# Gateway_HUB.net
KiCad netlist of a schematic drawn in EAGLE
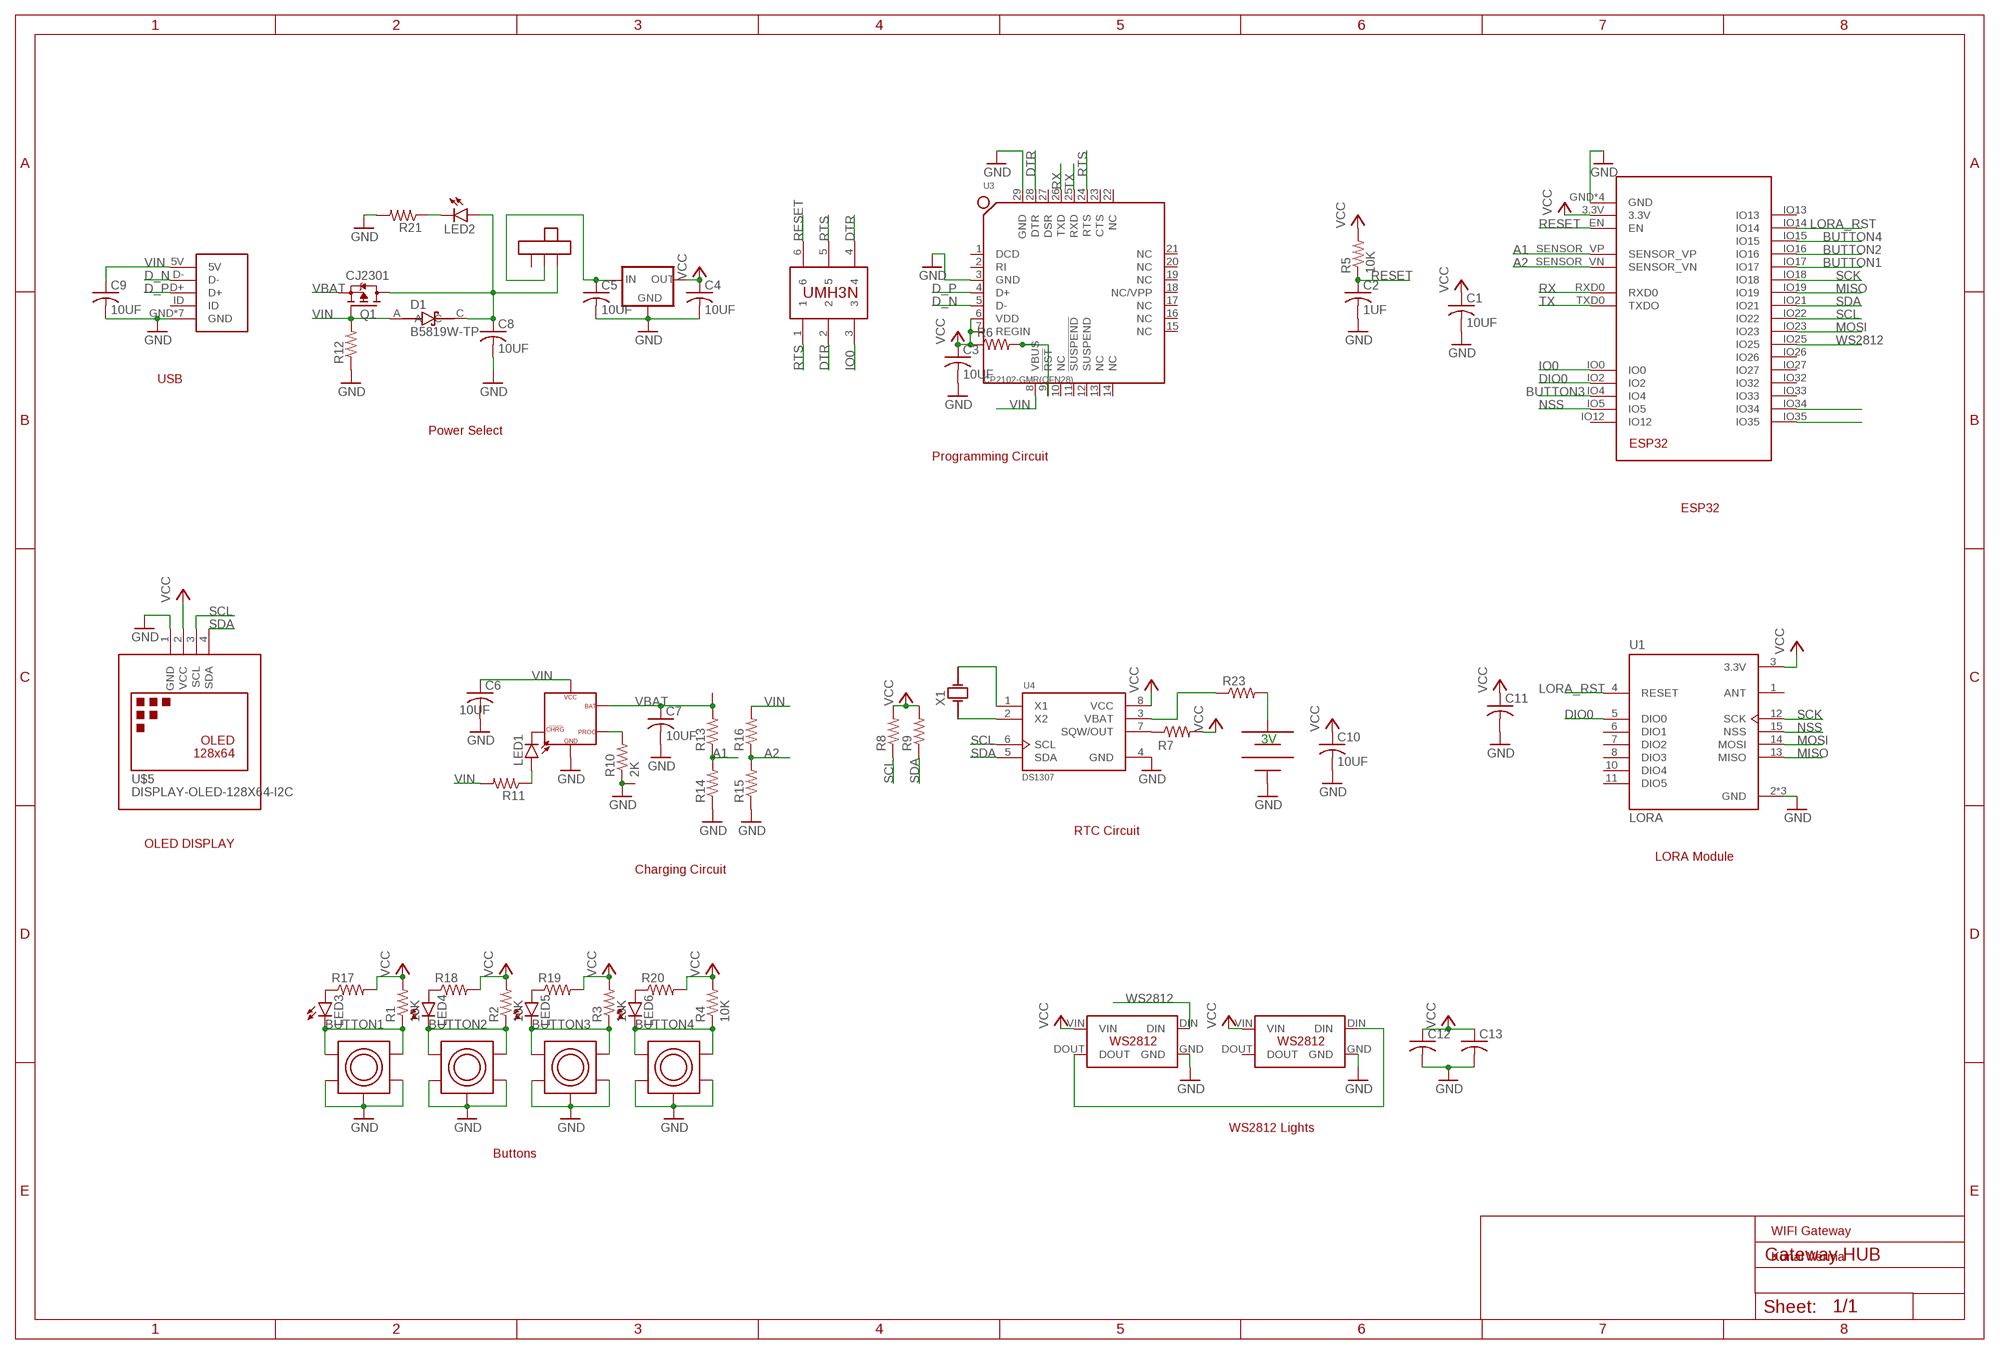
[diagram p0: schematic, sheet 1]

(export (version "E")
  (design (tool "Eeschema 10.0.6"))
  (components
    (comp (ref "C1")
      (value "10UF")
      (footprint "eagle-import:C0603")
      (libsource (lib "eagle-import") (part "C-USC0603"))
    )
    (comp (ref "C2")
      (value "1UF")
      (footprint "eagle-import:C0603")
      (libsource (lib "eagle-import") (part "C-USC0603"))
    )
    (comp (ref "C3")
      (value "10UF")
      (footprint "eagle-import:C0603")
      (libsource (lib "eagle-import") (part "C-USC0603"))
    )
    (comp (ref "C4")
      (value "10UF")
      (footprint "eagle-import:C0603")
      (libsource (lib "eagle-import") (part "C-USC0603"))
    )
    (comp (ref "C5")
      (value "10UF")
      (footprint "eagle-import:C0603")
      (libsource (lib "eagle-import") (part "C-USC0603"))
    )
    (comp (ref "C6")
      (value "10UF")
      (footprint "eagle-import:C0603")
      (libsource (lib "eagle-import") (part "C-USC0603"))
    )
    (comp (ref "C7")
      (value "10UF")
      (footprint "eagle-import:C0603")
      (libsource (lib "eagle-import") (part "C-USC0603"))
    )
    (comp (ref "C8")
      (value "10UF")
      (footprint "eagle-import:C0603")
      (libsource (lib "eagle-import") (part "C-USC0603"))
    )
    (comp (ref "C9")
      (value "10UF")
      (footprint "eagle-import:C0603")
      (libsource (lib "eagle-import") (part "C-USC0603"))
    )
    (comp (ref "C10")
      (value "10UF")
      (footprint "eagle-import:C0603")
      (libsource (lib "eagle-import") (part "C-USC0603"))
    )
    (comp (ref "C11")
      (value "C-USC0603")
      (footprint "eagle-import:C0603")
      (libsource (lib "eagle-import") (part "C-USC0603"))
    )
    (comp (ref "C12")
      (value "C-USC0603")
      (footprint "eagle-import:C0603")
      (libsource (lib "eagle-import") (part "C-USC0603"))
    )
    (comp (ref "C13")
      (value "C-USC0603")
      (footprint "eagle-import:C0603")
      (libsource (lib "eagle-import") (part "C-USC0603"))
    )
    (comp (ref "D1")
      (value "B5819W-TP")
      (footprint "eagle-import:SOD3716X135N")
      (fields (field (name "MF") "Micro Commercial"))
      (libsource (lib "eagle-import") (part "B5819W-TP"))
    )
    (comp (ref "IC1")
      (value "V_REG3.3MP")
      (footprint "eagle-import:SOT223")
      (fields (field (name "MF") "Texas Instruments") (field (name "MPN") "LM1117MP-3.3"))
      (libsource (lib "eagle-import") (part "V_REGMP3.3"))
    )
    (comp (ref "LED1")
      (value "LEDSML0603")
      (footprint "eagle-import:SML0603")
      (libsource (lib "eagle-import") (part "LEDSML0603"))
    )
    (comp (ref "LED2")
      (value "LEDSML0603")
      (footprint "eagle-import:SML0603")
      (libsource (lib "eagle-import") (part "LEDSML0603"))
    )
    (comp (ref "LED3")
      (value "LEDSML0603")
      (footprint "eagle-import:SML0603")
      (libsource (lib "eagle-import") (part "LEDSML0603"))
    )
    (comp (ref "LED4")
      (value "LEDSML0603")
      (footprint "eagle-import:SML0603")
      (libsource (lib "eagle-import") (part "LEDSML0603"))
    )
    (comp (ref "LED5")
      (value "LEDSML0603")
      (footprint "eagle-import:SML0603")
      (libsource (lib "eagle-import") (part "LEDSML0603"))
    )
    (comp (ref "LED6")
      (value "LEDSML0603")
      (footprint "eagle-import:SML0603")
      (libsource (lib "eagle-import") (part "LEDSML0603"))
    )
    (comp (ref "Q1")
      (value "CJ2301")
      (footprint "eagle-import:SOT95P230X110-3N")
      (fields (field (name "MF") "Nexperia USA Inc.") (field (name "MP") "PMV65XP,215"))
      (libsource (lib "eagle-import") (part "CJ2301"))
    )
    (comp (ref "R1")
      (value "10K")
      (footprint "eagle-import:R0603")
      (libsource (lib "eagle-import") (part "R-US_R0603"))
    )
    (comp (ref "R2")
      (value "10K")
      (footprint "eagle-import:R0603")
      (libsource (lib "eagle-import") (part "R-US_R0603"))
    )
    (comp (ref "R3")
      (value "10K")
      (footprint "eagle-import:R0603")
      (libsource (lib "eagle-import") (part "R-US_R0603"))
    )
    (comp (ref "R4")
      (value "10K")
      (footprint "eagle-import:R0603")
      (libsource (lib "eagle-import") (part "R-US_R0603"))
    )
    (comp (ref "R5")
      (value "10K")
      (footprint "eagle-import:R0603")
      (libsource (lib "eagle-import") (part "R-US_R0603"))
    )
    (comp (ref "R6")
      (value "R-US_R0603")
      (footprint "eagle-import:R0603")
      (libsource (lib "eagle-import") (part "R-US_R0603"))
    )
    (comp (ref "R7")
      (value "R-US_R0603")
      (footprint "eagle-import:R0603")
      (libsource (lib "eagle-import") (part "R-US_R0603"))
    )
    (comp (ref "R8")
      (value "R-US_R0603")
      (footprint "eagle-import:R0603")
      (libsource (lib "eagle-import") (part "R-US_R0603"))
    )
    (comp (ref "R9")
      (value "R-US_R0603")
      (footprint "eagle-import:R0603")
      (libsource (lib "eagle-import") (part "R-US_R0603"))
    )
    (comp (ref "R10")
      (value "2K")
      (footprint "eagle-import:R0603")
      (libsource (lib "eagle-import") (part "R-US_R0603"))
    )
    (comp (ref "R11")
      (value "R-US_R0603")
      (footprint "eagle-import:R0603")
      (libsource (lib "eagle-import") (part "R-US_R0603"))
    )
    (comp (ref "R12")
      (value "R-US_R0603")
      (footprint "eagle-import:R0603")
      (libsource (lib "eagle-import") (part "R-US_R0603"))
    )
    (comp (ref "R13")
      (value "R-US_R0603")
      (footprint "eagle-import:R0603")
      (libsource (lib "eagle-import") (part "R-US_R0603"))
    )
    (comp (ref "R14")
      (value "R-US_R0603")
      (footprint "eagle-import:R0603")
      (libsource (lib "eagle-import") (part "R-US_R0603"))
    )
    (comp (ref "R15")
      (value "R-US_R0603")
      (footprint "eagle-import:R0603")
      (libsource (lib "eagle-import") (part "R-US_R0603"))
    )
    (comp (ref "R16")
      (value "R-US_R0603")
      (footprint "eagle-import:R0603")
      (libsource (lib "eagle-import") (part "R-US_R0603"))
    )
    (comp (ref "R17")
      (value "R-US_R0603")
      (footprint "eagle-import:R0603")
      (libsource (lib "eagle-import") (part "R-US_R0603"))
    )
    (comp (ref "R18")
      (value "R-US_R0603")
      (footprint "eagle-import:R0603")
      (libsource (lib "eagle-import") (part "R-US_R0603"))
    )
    (comp (ref "R19")
      (value "R-US_R0603")
      (footprint "eagle-import:R0603")
      (libsource (lib "eagle-import") (part "R-US_R0603"))
    )
    (comp (ref "R20")
      (value "R-US_R0603")
      (footprint "eagle-import:R0603")
      (libsource (lib "eagle-import") (part "R-US_R0603"))
    )
    (comp (ref "R21")
      (value "R-US_R0603")
      (footprint "eagle-import:R0603")
      (libsource (lib "eagle-import") (part "R-US_R0603"))
    )
    (comp (ref "R23")
      (value "R-US_R0603")
      (footprint "eagle-import:R0603")
      (libsource (lib "eagle-import") (part "R-US_R0603"))
    )
    (comp (ref "U$1")
      (value "PUSHBUTTON")
      (footprint "eagle-import:B3W-4105")
      (libsource (lib "eagle-import") (part "PUSHBUTTON"))
    )
    (comp (ref "U$2")
      (value "PUSHBUTTON")
      (footprint "eagle-import:B3W-4105")
      (libsource (lib "eagle-import") (part "PUSHBUTTON"))
    )
    (comp (ref "U$3")
      (value "PUSHBUTTON")
      (footprint "eagle-import:B3W-4105")
      (libsource (lib "eagle-import") (part "PUSHBUTTON"))
    )
    (comp (ref "U$4")
      (value "PUSHBUTTON")
      (footprint "eagle-import:B3W-4105")
      (libsource (lib "eagle-import") (part "PUSHBUTTON"))
    )
    (comp (ref "U$5")
      (value "DISPLAY-OLED-128X64-I2C")
      (footprint "eagle-import:DISPLAY-OLED-128X64-I2C")
      (libsource (lib "eagle-import") (part "DISPLAY-OLED-128X64-I2C"))
    )
    (comp (ref "U$6")
      (value "COIN_CELL_HOLDER")
      (footprint "eagle-import:CR2032-BS-6-1")
      (libsource (lib "eagle-import") (part "COIN_CELL_HOLDER"))
    )
    (comp (ref "U$7")
      (value "UMH3N")
      (footprint "eagle-import:UMH3N")
      (libsource (lib "eagle-import") (part "UMH3N"))
    )
    (comp (ref "U$8")
      (value "MICROUSB")
      (footprint "eagle-import:USB")
      (libsource (lib "eagle-import") (part "MICROUSB"))
    )
    (comp (ref "U$9")
      (value "SELF-TOOGLE-SWITCH")
      (footprint "eagle-import:SELF-TOOGLE-SWITCH")
      (libsource (lib "eagle-import") (part "SELF-TOOGLE-SWITCH"))
    )
    (comp (ref "U$10")
      (value "PAD")
      (footprint "eagle-import:PADS")
      (libsource (lib "eagle-import") (part "PAD"))
    )
    (comp (ref "U$11")
      (value "PAD")
      (footprint "eagle-import:PADS")
      (libsource (lib "eagle-import") (part "PAD"))
    )
    (comp (ref "U$12")
      (value "WS2812SMD-2020")
      (footprint "eagle-import:SMD-2020")
      (libsource (lib "eagle-import") (part "WS2812SMD-2020"))
    )
    (comp (ref "U$13")
      (value "WS2812SMD-2020")
      (footprint "eagle-import:SMD-2020")
      (libsource (lib "eagle-import") (part "WS2812SMD-2020"))
    )
    (comp (ref "U1")
      (value "LORA")
      (footprint "eagle-import:XCVR_RA-01H")
      (fields (field (name "MF") "AI-Thinker") (field (name "MP") "RA-01H"))
      (libsource (lib "eagle-import") (part "LORA"))
    )
    (comp (ref "U2")
      (value "ESP32")
      (footprint "eagle-import:MODULE_ESP-WROOM-32")
      (libsource (lib "eagle-import") (part "ESP32"))
    )
    (comp (ref "U3")
      (value "CP2102-GMR(QFN28)")
      (footprint "eagle-import:QFN28G_0.5-5X5MM")
      (fields (field (name "MF") "Silicon") (field (name "MP") "CP2102-GMR"))
      (libsource (lib "eagle-import") (part "CP2102-GMR(QFN28)"))
    )
    (comp (ref "U4")
      (value "DS1307")
      (footprint "eagle-import:SOIC127P600X175-8N")
      (fields (field (name "MF") "Maxim Integrated") (field (name "MP") "DS1307Z"))
      (libsource (lib "eagle-import") (part "DS1307"))
    )
    (comp (ref "U5")
      (value "TP4054")
      (footprint "eagle-import:SOT23-3")
      (fields (field (name "MF") "Richtek USA") (field (name "MP") "RT9193-33GB"))
      (libsource (lib "eagle-import") (part "TP4054"))
    )
    (comp (ref "X1")
      (value "CRYSTAL_38T-32.768KHZ")
      (footprint "eagle-import:XTAL_AB38T-32.768KHZ")
      (fields (field (name "MF") "Abracon") (field (name "MP") "AB38T-32.768KHZ"))
      (libsource (lib "eagle-import") (part "CRYSTAL_38T-32.768KHZ"))
    )
  )
  (nets
    (net (code "1") (name "/A1") (class "Default")
      (node (ref "R13") (pin "1") (pinfunction "1_1") (pintype "passive"))
      (node (ref "R14") (pin "2") (pinfunction "2_2") (pintype "passive"))
      (node (ref "U2") (pin "SENSOR_VP") (pinfunction "SENSOR_VP_SENSOR_VP") (pintype "bidirectional"))
    )
    (net (code "2") (name "/A2") (class "Default")
      (node (ref "R15") (pin "2") (pinfunction "2_2") (pintype "passive"))
      (node (ref "R16") (pin "1") (pinfunction "1_1") (pintype "passive"))
      (node (ref "U2") (pin "SENSOR_VN") (pinfunction "SENSOR_VN_SENSOR_VN") (pintype "bidirectional"))
    )
    (net (code "3") (name "/BUTTON1") (class "Default")
      (node (ref "LED3") (pin "C") (pinfunction "C_C") (pintype "passive"))
      (node (ref "R1") (pin "1") (pinfunction "1_1") (pintype "passive"))
      (node (ref "U$1") (pin "P$1") (pinfunction "P$1_P$1") (pintype "bidirectional"))
      (node (ref "U$1") (pin "P$4") (pinfunction "P$4_P$4") (pintype "bidirectional"))
      (node (ref "U2") (pin "IO17") (pinfunction "IO17_IO17") (pintype "bidirectional"))
    )
    (net (code "4") (name "/BUTTON2") (class "Default")
      (node (ref "LED4") (pin "C") (pinfunction "C_C") (pintype "passive"))
      (node (ref "R2") (pin "1") (pinfunction "1_1") (pintype "passive"))
      (node (ref "U$2") (pin "P$1") (pinfunction "P$1_P$1") (pintype "bidirectional"))
      (node (ref "U$2") (pin "P$4") (pinfunction "P$4_P$4") (pintype "bidirectional"))
      (node (ref "U2") (pin "IO16") (pinfunction "IO16_IO16") (pintype "bidirectional"))
    )
    (net (code "5") (name "/BUTTON3") (class "Default")
      (node (ref "LED5") (pin "C") (pinfunction "C_C") (pintype "passive"))
      (node (ref "R3") (pin "1") (pinfunction "1_1") (pintype "passive"))
      (node (ref "U$3") (pin "P$1") (pinfunction "P$1_P$1") (pintype "bidirectional"))
      (node (ref "U$3") (pin "P$4") (pinfunction "P$4_P$4") (pintype "bidirectional"))
      (node (ref "U2") (pin "IO4") (pinfunction "IO4_IO4") (pintype "bidirectional"))
    )
    (net (code "6") (name "/BUTTON4") (class "Default")
      (node (ref "LED6") (pin "C") (pinfunction "C_C") (pintype "passive"))
      (node (ref "R4") (pin "1") (pinfunction "1_1") (pintype "passive"))
      (node (ref "U$4") (pin "P$1") (pinfunction "P$1_P$1") (pintype "bidirectional"))
      (node (ref "U$4") (pin "P$4") (pinfunction "P$4_P$4") (pintype "bidirectional"))
      (node (ref "U2") (pin "IO15") (pinfunction "IO15_IO15") (pintype "bidirectional"))
    )
    (net (code "7") (name "/DIO0") (class "Default")
      (node (ref "U1") (pin "5") (pinfunction "DIO0_5") (pintype "bidirectional"))
      (node (ref "U2") (pin "IO2") (pinfunction "IO2_IO2") (pintype "bidirectional"))
    )
    (net (code "8") (name "/DTR") (class "Default")
      (node (ref "U$7") (pin "2") (pinfunction "2_2") (pintype "bidirectional"))
      (node (ref "U$7") (pin "4") (pinfunction "4_4") (pintype "bidirectional"))
      (node (ref "U3") (pin "28") (pinfunction "DTR_28") (pintype "bidirectional"))
    )
    (net (code "9") (name "/D_N") (class "Default")
      (node (ref "U$8") (pin "D-") (pinfunction "D-_D-") (pintype "bidirectional"))
      (node (ref "U3") (pin "5") (pinfunction "D-_5") (pintype "bidirectional"))
    )
    (net (code "10") (name "/D_P") (class "Default")
      (node (ref "U$8") (pin "D+") (pinfunction "D+_D+") (pintype "bidirectional"))
      (node (ref "U3") (pin "4") (pinfunction "D+_4") (pintype "bidirectional"))
    )
    (net (code "11") (name "/IO0") (class "Default")
      (node (ref "U$7") (pin "3") (pinfunction "3_3") (pintype "bidirectional"))
      (node (ref "U2") (pin "IO0") (pinfunction "IO0_IO0") (pintype "bidirectional"))
    )
    (net (code "12") (name "/LORA_RST") (class "Default")
      (node (ref "U1") (pin "4") (pinfunction "RESET_4") (pintype "input"))
      (node (ref "U2") (pin "IO14") (pinfunction "IO14_IO14") (pintype "bidirectional"))
    )
    (net (code "13") (name "/MISO") (class "Default")
      (node (ref "U1") (pin "13") (pinfunction "MISO_13") (pintype "output"))
      (node (ref "U2") (pin "IO19") (pinfunction "IO19_IO19") (pintype "bidirectional"))
    )
    (net (code "14") (name "/MOSI") (class "Default")
      (node (ref "U1") (pin "14") (pinfunction "MOSI_14") (pintype "input"))
      (node (ref "U2") (pin "IO23") (pinfunction "IO23_IO23") (pintype "bidirectional"))
    )
    (net (code "15") (name "/NSS") (class "Default")
      (node (ref "U1") (pin "15") (pinfunction "NSS_15") (pintype "input"))
      (node (ref "U2") (pin "IO5") (pinfunction "IO5_IO5") (pintype "bidirectional"))
    )
    (net (code "16") (name "/RESET") (class "Default")
      (node (ref "C2") (pin "1") (pinfunction "1_1") (pintype "passive"))
      (node (ref "R5") (pin "1") (pinfunction "1_1") (pintype "passive"))
      (node (ref "U$7") (pin "6") (pinfunction "6_6") (pintype "bidirectional"))
      (node (ref "U2") (pin "EN") (pinfunction "EN_EN") (pintype "bidirectional"))
    )
    (net (code "17") (name "/RTS") (class "Default")
      (node (ref "U$7") (pin "1") (pinfunction "1_1") (pintype "bidirectional"))
      (node (ref "U$7") (pin "5") (pinfunction "5_5") (pintype "bidirectional"))
      (node (ref "U3") (pin "24") (pinfunction "RTS_24") (pintype "bidirectional"))
    )
    (net (code "18") (name "/RX") (class "Default")
      (node (ref "U2") (pin "RXD0") (pinfunction "RXD0_RXD0") (pintype "bidirectional"))
      (node (ref "U3") (pin "26") (pinfunction "TXD_26") (pintype "bidirectional"))
    )
    (net (code "19") (name "/SCK") (class "Default")
      (node (ref "U1") (pin "12") (pinfunction "SCK_12") (pintype "input"))
      (node (ref "U2") (pin "IO18") (pinfunction "IO18_IO18") (pintype "bidirectional"))
    )
    (net (code "20") (name "/SCL") (class "Default")
      (node (ref "R8") (pin "1") (pinfunction "1_1") (pintype "passive"))
      (node (ref "U$5") (pin "3") (pinfunction "SCL_3") (pintype "bidirectional"))
      (node (ref "U2") (pin "IO22") (pinfunction "IO22_IO22") (pintype "bidirectional"))
      (node (ref "U4") (pin "6") (pinfunction "SCL_6") (pintype "input"))
    )
    (net (code "21") (name "/SDA") (class "Default")
      (node (ref "R9") (pin "1") (pinfunction "1_1") (pintype "passive"))
      (node (ref "U$5") (pin "4") (pinfunction "SDA_4") (pintype "bidirectional"))
      (node (ref "U2") (pin "IO21") (pinfunction "IO21_IO21") (pintype "bidirectional"))
      (node (ref "U4") (pin "5") (pinfunction "SDA_5") (pintype "bidirectional"))
    )
    (net (code "22") (name "/TX") (class "Default")
      (node (ref "U2") (pin "TXD0") (pinfunction "TXDO_TXD0") (pintype "bidirectional"))
      (node (ref "U3") (pin "25") (pinfunction "RXD_25") (pintype "bidirectional"))
    )
    (net (code "23") (name "/VBAT") (class "Default")
      (node (ref "C7") (pin "1") (pinfunction "1_1") (pintype "passive"))
      (node (ref "Q1") (pin "2") (pinfunction "S_2") (pintype "passive"))
      (node (ref "R13") (pin "2") (pinfunction "2_2") (pintype "passive"))
      (node (ref "U$10") (pin "P$1") (pinfunction "P$1_P$1") (pintype "bidirectional"))
      (node (ref "U5") (pin "3") (pinfunction "3_3") (pintype "bidirectional"))
    )
    (net (code "24") (name "/VIN") (class "Default")
      (node (ref "C6") (pin "1") (pinfunction "1_1") (pintype "passive"))
      (node (ref "C9") (pin "1") (pinfunction "1_1") (pintype "passive"))
      (node (ref "D1") (pin "A") (pinfunction "A_A") (pintype "passive"))
      (node (ref "Q1") (pin "1") (pinfunction "G_1") (pintype "passive"))
      (node (ref "R11") (pin "2") (pinfunction "2_2") (pintype "passive"))
      (node (ref "R12") (pin "2") (pinfunction "2_2") (pintype "passive"))
      (node (ref "R16") (pin "2") (pinfunction "2_2") (pintype "passive"))
      (node (ref "U$8") (pin "5V") (pinfunction "5V_5V") (pintype "bidirectional"))
      (node (ref "U3") (pin "8") (pinfunction "VBUS_8") (pintype "bidirectional"))
      (node (ref "U5") (pin "4") (pinfunction "4_4") (pintype "bidirectional"))
    )
    (net (code "25") (name "/WS2812") (class "Default")
      (node (ref "U$12") (pin "DIN") (pinfunction "DIN_DIN") (pintype "bidirectional"))
      (node (ref "U2") (pin "IO25") (pinfunction "IO25_IO25") (pintype "bidirectional"))
    )
    (net (code "26") (name "GND") (class "Default")
      (node (ref "C1") (pin "2") (pinfunction "2_2") (pintype "passive"))
      (node (ref "C10") (pin "2") (pinfunction "2_2") (pintype "passive"))
      (node (ref "C11") (pin "2") (pinfunction "2_2") (pintype "passive"))
      (node (ref "C12") (pin "2") (pinfunction "2_2") (pintype "passive"))
      (node (ref "C13") (pin "2") (pinfunction "2_2") (pintype "passive"))
      (node (ref "C2") (pin "2") (pinfunction "2_2") (pintype "passive"))
      (node (ref "C3") (pin "2") (pinfunction "2_2") (pintype "passive"))
      (node (ref "C4") (pin "2") (pinfunction "2_2") (pintype "passive"))
      (node (ref "C5") (pin "2") (pinfunction "2_2") (pintype "passive"))
      (node (ref "C6") (pin "2") (pinfunction "2_2") (pintype "passive"))
      (node (ref "C7") (pin "2") (pinfunction "2_2") (pintype "passive"))
      (node (ref "C8") (pin "2") (pinfunction "2_2") (pintype "passive"))
      (node (ref "C9") (pin "2") (pinfunction "2_2") (pintype "passive"))
      (node (ref "IC1") (pin "GND") (pinfunction "GND_GND") (pintype "input"))
      (node (ref "R10") (pin "1") (pinfunction "1_1") (pintype "passive"))
      (node (ref "R12") (pin "1") (pinfunction "1_1") (pintype "passive"))
      (node (ref "R14") (pin "1") (pinfunction "1_1") (pintype "passive"))
      (node (ref "R15") (pin "1") (pinfunction "1_1") (pintype "passive"))
      (node (ref "R21") (pin "2") (pinfunction "2_2") (pintype "passive"))
      (node (ref "U$1") (pin "P$2") (pinfunction "P$2_P$2") (pintype "bidirectional"))
      (node (ref "U$1") (pin "P$3") (pinfunction "P$3_P$3") (pintype "bidirectional"))
      (node (ref "U$1") (pin "P$5") (pinfunction "P$5_P$5") (pintype "bidirectional"))
      (node (ref "U$11") (pin "P$1") (pinfunction "P$1_P$1") (pintype "bidirectional"))
      (node (ref "U$12") (pin "GND") (pinfunction "GND_GND") (pintype "bidirectional"))
      (node (ref "U$13") (pin "GND") (pinfunction "GND_GND") (pintype "bidirectional"))
      (node (ref "U$2") (pin "P$2") (pinfunction "P$2_P$2") (pintype "bidirectional"))
      (node (ref "U$2") (pin "P$3") (pinfunction "P$3_P$3") (pintype "bidirectional"))
      (node (ref "U$2") (pin "P$5") (pinfunction "P$5_P$5") (pintype "bidirectional"))
      (node (ref "U$3") (pin "P$2") (pinfunction "P$2_P$2") (pintype "bidirectional"))
      (node (ref "U$3") (pin "P$3") (pinfunction "P$3_P$3") (pintype "bidirectional"))
      (node (ref "U$3") (pin "P$5") (pinfunction "P$5_P$5") (pintype "bidirectional"))
      (node (ref "U$4") (pin "P$2") (pinfunction "P$2_P$2") (pintype "bidirectional"))
      (node (ref "U$4") (pin "P$3") (pinfunction "P$3_P$3") (pintype "bidirectional"))
      (node (ref "U$4") (pin "P$5") (pinfunction "P$5_P$5") (pintype "bidirectional"))
      (node (ref "U$5") (pin "1") (pinfunction "GND_1") (pintype "power_in"))
      (node (ref "U$6") (pin "-") (pinfunction "-_-") (pintype "bidirectional"))
      (node (ref "U$8") (pin "GND") (pinfunction "GND_GND") (pintype "bidirectional"))
      (node (ref "U$8") (pin "GND1") (pinfunction "GND_GND1") (pintype "bidirectional"))
      (node (ref "U$8") (pin "GND2") (pinfunction "GND_GND2") (pintype "bidirectional"))
      (node (ref "U$8") (pin "GND3") (pinfunction "GND_GND3") (pintype "bidirectional"))
      (node (ref "U$8") (pin "GND4") (pinfunction "GND_GND4") (pintype "bidirectional"))
      (node (ref "U$8") (pin "GND5") (pinfunction "GND_GND5") (pintype "bidirectional"))
      (node (ref "U$8") (pin "GND6") (pinfunction "GND_GND6") (pintype "bidirectional"))
      (node (ref "U1") (pin "16") (pinfunction "GND_16") (pintype "power_in"))
      (node (ref "U1") (pin "2") (pinfunction "GND_2") (pintype "power_in"))
      (node (ref "U1") (pin "9") (pinfunction "GND_9") (pintype "power_in"))
      (node (ref "U2") (pin "GND") (pinfunction "GND_GND") (pintype "bidirectional"))
      (node (ref "U2") (pin "GND1") (pinfunction "GND_GND1") (pintype "bidirectional"))
      (node (ref "U2") (pin "GND2") (pinfunction "GND_GND2") (pintype "bidirectional"))
      (node (ref "U2") (pin "GND3") (pinfunction "GND_GND3") (pintype "bidirectional"))
      (node (ref "U3") (pin "29") (pinfunction "GND_29") (pintype "bidirectional"))
      (node (ref "U3") (pin "3") (pinfunction "GND_3") (pintype "bidirectional"))
      (node (ref "U4") (pin "4") (pinfunction "GND_4") (pintype "power_in"))
      (node (ref "U5") (pin "2") (pinfunction "2_2") (pintype "bidirectional"))
    )
    (net (code "27") (name "Net-(IC1-IN)") (class "Default")
      (node (ref "C5") (pin "1") (pinfunction "1_1") (pintype "passive"))
      (node (ref "IC1") (pin "VIN") (pinfunction "IN_VIN") (pintype "input"))
      (node (ref "U$9") (pin "2") (pinfunction "2_2") (pintype "bidirectional"))
    )
    (net (code "28") (name "Net-(LED1-PadA)") (class "Default")
      (node (ref "LED1") (pin "A") (pinfunction "A_A") (pintype "passive"))
      (node (ref "R11") (pin "1") (pinfunction "1_1") (pintype "passive"))
    )
    (net (code "29") (name "Net-(LED1-PadC)") (class "Default")
      (node (ref "LED1") (pin "C") (pinfunction "C_C") (pintype "passive"))
      (node (ref "U5") (pin "1") (pinfunction "1_1") (pintype "bidirectional"))
    )
    (net (code "30") (name "Net-(LED2-PadC)") (class "Default")
      (node (ref "LED2") (pin "C") (pinfunction "C_C") (pintype "passive"))
      (node (ref "R21") (pin "1") (pinfunction "1_1") (pintype "passive"))
    )
    (net (code "31") (name "Net-(LED3-PadA)") (class "Default")
      (node (ref "LED3") (pin "A") (pinfunction "A_A") (pintype "passive"))
      (node (ref "R17") (pin "1") (pinfunction "1_1") (pintype "passive"))
    )
    (net (code "32") (name "Net-(LED4-PadA)") (class "Default")
      (node (ref "LED4") (pin "A") (pinfunction "A_A") (pintype "passive"))
      (node (ref "R18") (pin "1") (pinfunction "1_1") (pintype "passive"))
    )
    (net (code "33") (name "Net-(LED5-PadA)") (class "Default")
      (node (ref "LED5") (pin "A") (pinfunction "A_A") (pintype "passive"))
      (node (ref "R19") (pin "1") (pinfunction "1_1") (pintype "passive"))
    )
    (net (code "34") (name "Net-(LED6-PadA)") (class "Default")
      (node (ref "LED6") (pin "A") (pinfunction "A_A") (pintype "passive"))
      (node (ref "R20") (pin "1") (pinfunction "1_1") (pintype "passive"))
    )
    (net (code "35") (name "Net-(Q1-D)") (class "Default")
      (node (ref "C8") (pin "1") (pinfunction "1_1") (pintype "passive"))
      (node (ref "D1") (pin "C") (pinfunction "C_C") (pintype "passive"))
      (node (ref "LED2") (pin "A") (pinfunction "A_A") (pintype "passive"))
      (node (ref "Q1") (pin "3") (pinfunction "D_3") (pintype "passive"))
      (node (ref "U$9") (pin "3") (pinfunction "3_3") (pintype "bidirectional"))
    )
    (net (code "36") (name "Net-(R10-Pad2)") (class "Default")
      (node (ref "R10") (pin "2") (pinfunction "2_2") (pintype "passive"))
      (node (ref "U5") (pin "5") (pinfunction "5_5") (pintype "bidirectional"))
    )
    (net (code "37") (name "Net-(R23-Pad2)") (class "Default")
      (node (ref "R23") (pin "2") (pinfunction "2_2") (pintype "passive"))
      (node (ref "U$6") (pin "+") (pinfunction "+_+") (pintype "bidirectional"))
    )
    (net (code "38") (name "Net-(U$12-PadDOUT)") (class "Default")
      (node (ref "U$12") (pin "DOUT") (pinfunction "DOUT_DOUT") (pintype "bidirectional"))
      (node (ref "U$13") (pin "DIN") (pinfunction "DIN_DIN") (pintype "bidirectional"))
    )
    (net (code "39") (name "Net-(U3-~{RST})") (class "Default")
      (node (ref "R6") (pin "2") (pinfunction "2_2") (pintype "passive"))
      (node (ref "U3") (pin "9") (pinfunction "~{RST}_9") (pintype "bidirectional"))
    )
    (net (code "40") (name "Net-(U4-SQW{slash}OUT)") (class "Default")
      (node (ref "R7") (pin "1") (pinfunction "1_1") (pintype "passive"))
      (node (ref "U4") (pin "7") (pinfunction "SQW/OUT_7") (pintype "output"))
    )
    (net (code "41") (name "Net-(U4-VBAT)") (class "Default")
      (node (ref "R23") (pin "1") (pinfunction "1_1") (pintype "passive"))
      (node (ref "U4") (pin "3") (pinfunction "VBAT_3") (pintype "power_in"))
    )
    (net (code "42") (name "Net-(U4-X1)") (class "Default")
      (node (ref "U4") (pin "1") (pinfunction "X1_1") (pintype "input"))
      (node (ref "X1") (pin "2") (pinfunction "2_2") (pintype "passive"))
    )
    (net (code "43") (name "Net-(U4-X2)") (class "Default")
      (node (ref "U4") (pin "2") (pinfunction "X2_2") (pintype "input"))
      (node (ref "X1") (pin "1") (pinfunction "1_1") (pintype "passive"))
    )
    (net (code "44") (name "VCC") (class "Default")
      (node (ref "C1") (pin "1") (pinfunction "1_1") (pintype "passive"))
      (node (ref "C10") (pin "1") (pinfunction "1_1") (pintype "passive"))
      (node (ref "C11") (pin "1") (pinfunction "1_1") (pintype "passive"))
      (node (ref "C12") (pin "1") (pinfunction "1_1") (pintype "passive"))
      (node (ref "C13") (pin "1") (pinfunction "1_1") (pintype "passive"))
      (node (ref "C3") (pin "1") (pinfunction "1_1") (pintype "passive"))
      (node (ref "C4") (pin "1") (pinfunction "1_1") (pintype "passive"))
      (node (ref "IC1") (pin "VOUT") (pinfunction "OUT_VOUT") (pintype "passive"))
      (node (ref "IC1") (pin "VOUT1") (pinfunction "OUT_VOUT1") (pintype "passive"))
      (node (ref "R1") (pin "2") (pinfunction "2_2") (pintype "passive"))
      (node (ref "R17") (pin "2") (pinfunction "2_2") (pintype "passive"))
      (node (ref "R18") (pin "2") (pinfunction "2_2") (pintype "passive"))
      (node (ref "R19") (pin "2") (pinfunction "2_2") (pintype "passive"))
      (node (ref "R2") (pin "2") (pinfunction "2_2") (pintype "passive"))
      (node (ref "R20") (pin "2") (pinfunction "2_2") (pintype "passive"))
      (node (ref "R3") (pin "2") (pinfunction "2_2") (pintype "passive"))
      (node (ref "R4") (pin "2") (pinfunction "2_2") (pintype "passive"))
      (node (ref "R5") (pin "2") (pinfunction "2_2") (pintype "passive"))
      (node (ref "R6") (pin "1") (pinfunction "1_1") (pintype "passive"))
      (node (ref "R7") (pin "2") (pinfunction "2_2") (pintype "passive"))
      (node (ref "R8") (pin "2") (pinfunction "2_2") (pintype "passive"))
      (node (ref "R9") (pin "2") (pinfunction "2_2") (pintype "passive"))
      (node (ref "U$12") (pin "VIN") (pinfunction "VIN_VIN") (pintype "bidirectional"))
      (node (ref "U$13") (pin "VIN") (pinfunction "VIN_VIN") (pintype "bidirectional"))
      (node (ref "U$5") (pin "2") (pinfunction "VCC_2") (pintype "power_in"))
      (node (ref "U1") (pin "3") (pinfunction "3.3V_3") (pintype "power_in"))
      (node (ref "U2") (pin "3.3V") (pinfunction "3.3V_3.3V") (pintype "bidirectional"))
      (node (ref "U3") (pin "6") (pinfunction "VDD_6") (pintype "bidirectional"))
      (node (ref "U3") (pin "7") (pinfunction "REGIN_7") (pintype "bidirectional"))
      (node (ref "U4") (pin "8") (pinfunction "VCC_8") (pintype "power_in"))
    )
    (net (code "45") (name "unconnected-(U$8-PadID)") (class "Default")
      (node (ref "U$8") (pin "ID") (pinfunction "ID_ID") (pintype "bidirectional"))
    )
    (net (code "46") (name "unconnected-(U$9-Pad1)") (class "Default")
      (node (ref "U$9") (pin "1") (pinfunction "1_1") (pintype "bidirectional"))
    )
    (net (code "47") (name "unconnected-(U$13-PadDOUT)") (class "Default")
      (node (ref "U$13") (pin "DOUT") (pinfunction "DOUT_DOUT") (pintype "bidirectional"))
    )
    (net (code "48") (name "unconnected-(U1-ANT-Pad1)") (class "Default")
      (node (ref "U1") (pin "1") (pinfunction "ANT_1") (pintype "bidirectional"))
    )
    (net (code "49") (name "unconnected-(U1-DIO1-Pad6)") (class "Default")
      (node (ref "U1") (pin "6") (pinfunction "DIO1_6") (pintype "bidirectional"))
    )
    (net (code "50") (name "unconnected-(U1-DIO2-Pad7)") (class "Default")
      (node (ref "U1") (pin "7") (pinfunction "DIO2_7") (pintype "bidirectional"))
    )
    (net (code "51") (name "unconnected-(U1-DIO3-Pad8)") (class "Default")
      (node (ref "U1") (pin "8") (pinfunction "DIO3_8") (pintype "bidirectional"))
    )
    (net (code "52") (name "unconnected-(U1-DIO4-Pad10)") (class "Default")
      (node (ref "U1") (pin "10") (pinfunction "DIO4_10") (pintype "bidirectional"))
    )
    (net (code "53") (name "unconnected-(U1-DIO5-Pad11)") (class "Default")
      (node (ref "U1") (pin "11") (pinfunction "DIO5_11") (pintype "bidirectional"))
    )
    (net (code "54") (name "unconnected-(U2-PadIO12)") (class "Default")
      (node (ref "U2") (pin "IO12") (pinfunction "IO12_IO12") (pintype "bidirectional"))
    )
    (net (code "55") (name "unconnected-(U2-PadIO13)") (class "Default")
      (node (ref "U2") (pin "IO13") (pinfunction "IO13_IO13") (pintype "bidirectional"))
    )
    (net (code "56") (name "unconnected-(U2-PadIO26)") (class "Default")
      (node (ref "U2") (pin "IO26") (pinfunction "IO26_IO26") (pintype "bidirectional"))
    )
    (net (code "57") (name "unconnected-(U2-PadIO27)") (class "Default")
      (node (ref "U2") (pin "IO27") (pinfunction "IO27_IO27") (pintype "bidirectional"))
    )
    (net (code "58") (name "unconnected-(U2-PadIO32)") (class "Default")
      (node (ref "U2") (pin "IO32") (pinfunction "IO32_IO32") (pintype "bidirectional"))
    )
    (net (code "59") (name "unconnected-(U2-PadIO33)") (class "Default")
      (node (ref "U2") (pin "IO33") (pinfunction "IO33_IO33") (pintype "bidirectional"))
    )
    (net (code "60") (name "unconnected-(U2-PadIO34)") (class "Default")
      (node (ref "U2") (pin "IO34") (pinfunction "IO34_IO34") (pintype "bidirectional"))
    )
    (net (code "61") (name "unconnected-(U2-PadIO35)") (class "Default")
      (node (ref "U2") (pin "IO35") (pinfunction "IO35_IO35") (pintype "bidirectional"))
    )
    (net (code "62") (name "unconnected-(U3-CTS-Pad23)") (class "Default")
      (node (ref "U3") (pin "23") (pinfunction "CTS_23") (pintype "bidirectional"))
    )
    (net (code "63") (name "unconnected-(U3-DCD-Pad1)") (class "Default")
      (node (ref "U3") (pin "1") (pinfunction "DCD_1") (pintype "bidirectional"))
    )
    (net (code "64") (name "unconnected-(U3-DSR-Pad27)") (class "Default")
      (node (ref "U3") (pin "27") (pinfunction "DSR_27") (pintype "bidirectional"))
    )
    (net (code "65") (name "unconnected-(U3-NC-Pad10)") (class "Default")
      (node (ref "U3") (pin "10") (pinfunction "NC_10") (pintype "bidirectional"))
    )
    (net (code "66") (name "unconnected-(U3-NC-Pad13)") (class "Default")
      (node (ref "U3") (pin "13") (pinfunction "NC_13") (pintype "bidirectional"))
    )
    (net (code "67") (name "unconnected-(U3-NC-Pad14)") (class "Default")
      (node (ref "U3") (pin "14") (pinfunction "NC_14") (pintype "bidirectional"))
    )
    (net (code "68") (name "unconnected-(U3-NC-Pad15)") (class "Default")
      (node (ref "U3") (pin "15") (pinfunction "NC_15") (pintype "bidirectional"))
    )
    (net (code "69") (name "unconnected-(U3-NC-Pad16)") (class "Default")
      (node (ref "U3") (pin "16") (pinfunction "NC_16") (pintype "bidirectional"))
    )
    (net (code "70") (name "unconnected-(U3-NC-Pad17)") (class "Default")
      (node (ref "U3") (pin "17") (pinfunction "NC_17") (pintype "bidirectional"))
    )
    (net (code "71") (name "unconnected-(U3-NC-Pad19)") (class "Default")
      (node (ref "U3") (pin "19") (pinfunction "NC_19") (pintype "bidirectional"))
    )
    (net (code "72") (name "unconnected-(U3-NC-Pad20)") (class "Default")
      (node (ref "U3") (pin "20") (pinfunction "NC_20") (pintype "bidirectional"))
    )
    (net (code "73") (name "unconnected-(U3-NC-Pad21)") (class "Default")
      (node (ref "U3") (pin "21") (pinfunction "NC_21") (pintype "bidirectional"))
    )
    (net (code "74") (name "unconnected-(U3-NC-Pad22)") (class "Default")
      (node (ref "U3") (pin "22") (pinfunction "NC_22") (pintype "bidirectional"))
    )
    (net (code "75") (name "unconnected-(U3-NC{slash}VPP-Pad18)") (class "Default")
      (node (ref "U3") (pin "18") (pinfunction "NC/VPP_18") (pintype "bidirectional"))
    )
    (net (code "76") (name "unconnected-(U3-RI-Pad2)") (class "Default")
      (node (ref "U3") (pin "2") (pinfunction "RI_2") (pintype "bidirectional"))
    )
    (net (code "77") (name "unconnected-(U3-SUSPEND-Pad12)") (class "Default")
      (node (ref "U3") (pin "12") (pinfunction "SUSPEND_12") (pintype "bidirectional"))
    )
    (net (code "78") (name "unconnected-(U3-~{SUSPEND}-Pad11)") (class "Default")
      (node (ref "U3") (pin "11") (pinfunction "~{SUSPEND}_11") (pintype "bidirectional"))
    )
  )
)
